# CON_SODIMM_200PIN_MO-224.net
KiCad netlist of a schematic drawn in Altium Designer
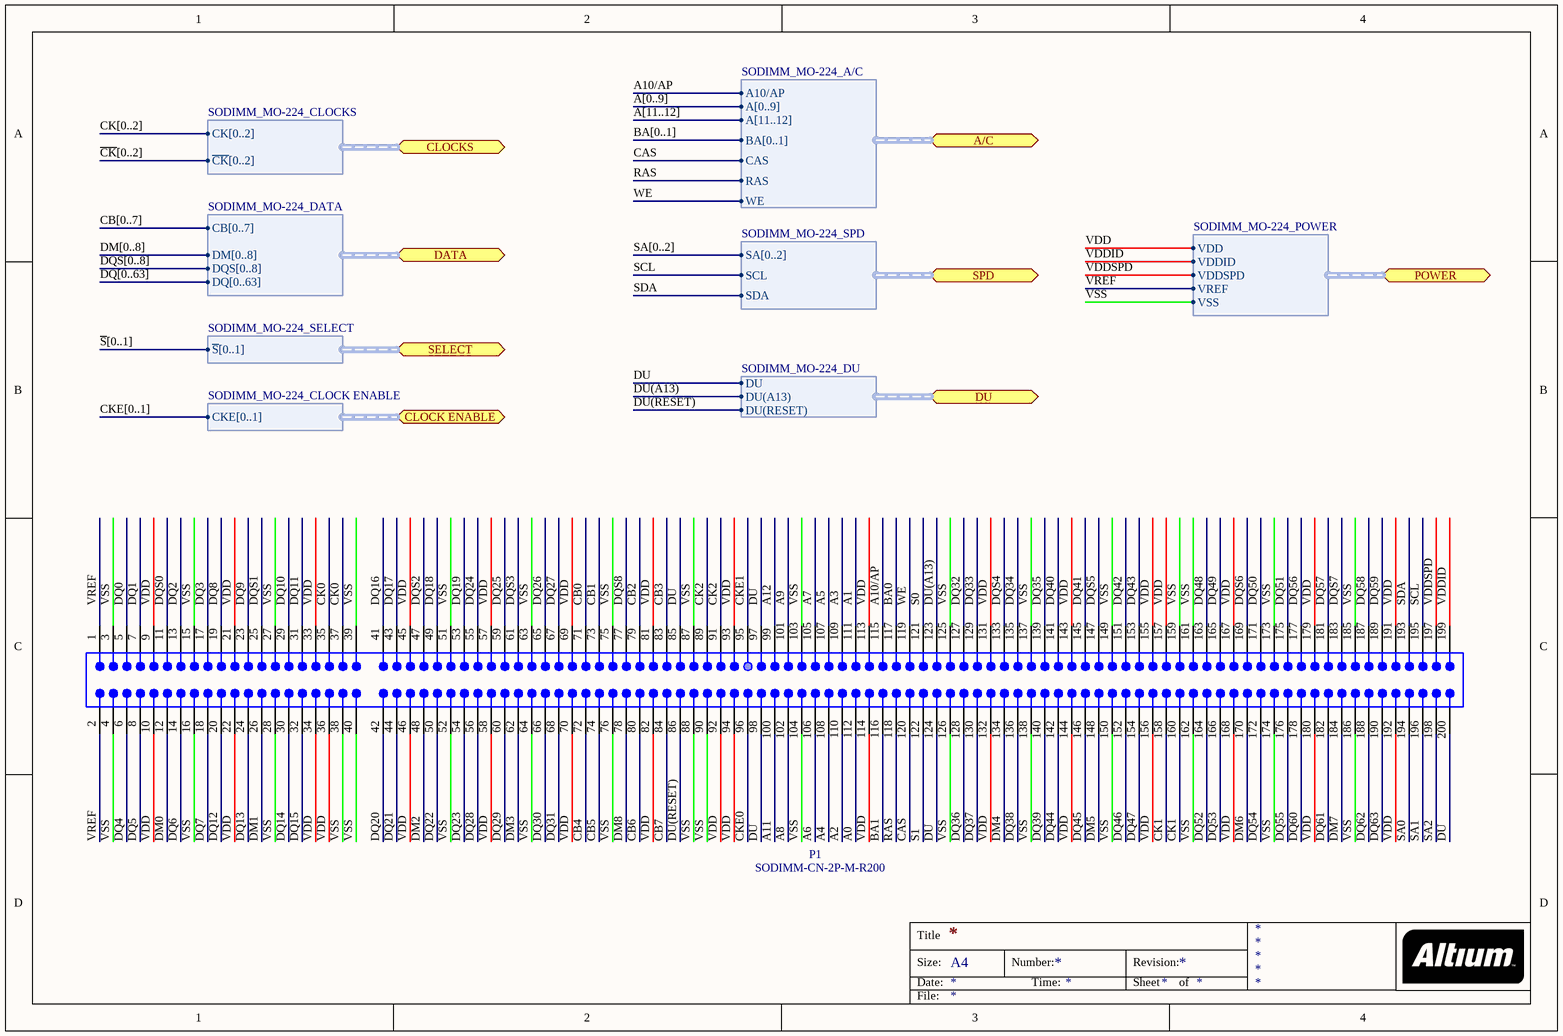
[diagram p0: CON_SODIMM_200PIN_MO-224.SchDoc]

(export (version "E")
  (design (tool "Eeschema 10.0.6"))
  (components
    (comp (ref "P1")
      (value "SODIMM-CN-2P-M-R200")
      (footprint "SODIMM-GF-2D-600-1K-S200")
      (description "Golden finger, SODIMM, Dual, Staggered, Pitch 0.6mm, 200-Position")
      (fields (field (name "PUBLISHER") "Altium"))
      (libsource (lib "Altium Shanghai") (part "SODIMM-CN-2S-M-R200"))
    )
  )
  (nets
    (net (code "10") (name "/A0") (class "Default")
      (node (ref "P1") (pin "112") (pinfunction "112_112") (pintype "passive"))
    )
    (net (code "11") (name "/A1") (class "Default")
      (node (ref "P1") (pin "111") (pinfunction "111_111") (pintype "passive"))
    )
    (net (code "12") (name "/A2") (class "Default")
      (node (ref "P1") (pin "110") (pinfunction "110_110") (pintype "passive"))
    )
    (net (code "13") (name "/A3") (class "Default")
      (node (ref "P1") (pin "109") (pinfunction "109_109") (pintype "passive"))
    )
    (net (code "14") (name "/A4") (class "Default")
      (node (ref "P1") (pin "108") (pinfunction "108_108") (pintype "passive"))
    )
    (net (code "15") (name "/A5") (class "Default")
      (node (ref "P1") (pin "107") (pinfunction "107_107") (pintype "passive"))
    )
    (net (code "16") (name "/A6") (class "Default")
      (node (ref "P1") (pin "106") (pinfunction "106_106") (pintype "passive"))
    )
    (net (code "17") (name "/A7") (class "Default")
      (node (ref "P1") (pin "105") (pinfunction "105_105") (pintype "passive"))
    )
    (net (code "18") (name "/A8") (class "Default")
      (node (ref "P1") (pin "102") (pinfunction "102_102") (pintype "passive"))
    )
    (net (code "19") (name "/A9") (class "Default")
      (node (ref "P1") (pin "101") (pinfunction "101_101") (pintype "passive"))
    )
    (net (code "20") (name "/A10{slash}AP") (class "Default")
      (node (ref "P1") (pin "115") (pinfunction "115_115") (pintype "passive"))
    )
    (net (code "21") (name "/A11") (class "Default")
      (node (ref "P1") (pin "100") (pinfunction "100_100") (pintype "passive"))
    )
    (net (code "22") (name "/A12") (class "Default")
      (node (ref "P1") (pin "99") (pinfunction "99_99") (pintype "passive"))
    )
    (net (code "25") (name "/BA0") (class "Default")
      (node (ref "P1") (pin "117") (pinfunction "117_117") (pintype "passive"))
    )
    (net (code "26") (name "/BA1") (class "Default")
      (node (ref "P1") (pin "116") (pinfunction "116_116") (pintype "passive"))
    )
    (net (code "28") (name "/CAS") (class "Default")
      (node (ref "P1") (pin "120") (pinfunction "120_120") (pintype "passive"))
    )
    (net (code "29") (name "/CB0") (class "Default")
      (node (ref "P1") (pin "71") (pinfunction "71_71") (pintype "passive"))
    )
    (net (code "30") (name "/CB1") (class "Default")
      (node (ref "P1") (pin "73") (pinfunction "73_73") (pintype "passive"))
    )
    (net (code "31") (name "/CB2") (class "Default")
      (node (ref "P1") (pin "79") (pinfunction "79_79") (pintype "passive"))
    )
    (net (code "32") (name "/CB3") (class "Default")
      (node (ref "P1") (pin "83") (pinfunction "83_83") (pintype "passive"))
    )
    (net (code "33") (name "/CB4") (class "Default")
      (node (ref "P1") (pin "72") (pinfunction "72_72") (pintype "passive"))
    )
    (net (code "34") (name "/CB5") (class "Default")
      (node (ref "P1") (pin "74") (pinfunction "74_74") (pintype "passive"))
    )
    (net (code "35") (name "/CB6") (class "Default")
      (node (ref "P1") (pin "80") (pinfunction "80_80") (pintype "passive"))
    )
    (net (code "36") (name "/CB7") (class "Default")
      (node (ref "P1") (pin "84") (pinfunction "84_84") (pintype "passive"))
    )
    (net (code "38") (name "/CK0") (class "Default")
      (node (ref "P1") (pin "35") (pinfunction "35_35") (pintype "passive"))
    )
    (net (code "39") (name "/CK1") (class "Default")
      (node (ref "P1") (pin "160") (pinfunction "160_160") (pintype "passive"))
    )
    (net (code "40") (name "/CK2") (class "Default")
      (node (ref "P1") (pin "89") (pinfunction "89_89") (pintype "passive"))
    )
    (net (code "41") (name "/CKE0") (class "Default")
      (node (ref "P1") (pin "96") (pinfunction "96_96") (pintype "passive"))
    )
    (net (code "42") (name "/CKE1") (class "Default")
      (node (ref "P1") (pin "95") (pinfunction "95_95") (pintype "passive"))
    )
    (net (code "45") (name "/DM0") (class "Default")
      (node (ref "P1") (pin "12") (pinfunction "12_12") (pintype "passive"))
    )
    (net (code "46") (name "/DM1") (class "Default")
      (node (ref "P1") (pin "26") (pinfunction "26_26") (pintype "passive"))
    )
    (net (code "47") (name "/DM2") (class "Default")
      (node (ref "P1") (pin "48") (pinfunction "48_48") (pintype "passive"))
    )
    (net (code "48") (name "/DM3") (class "Default")
      (node (ref "P1") (pin "62") (pinfunction "62_62") (pintype "passive"))
    )
    (net (code "49") (name "/DM4") (class "Default")
      (node (ref "P1") (pin "134") (pinfunction "134_134") (pintype "passive"))
    )
    (net (code "50") (name "/DM5") (class "Default")
      (node (ref "P1") (pin "148") (pinfunction "148_148") (pintype "passive"))
    )
    (net (code "51") (name "/DM6") (class "Default")
      (node (ref "P1") (pin "170") (pinfunction "170_170") (pintype "passive"))
    )
    (net (code "52") (name "/DM7") (class "Default")
      (node (ref "P1") (pin "184") (pinfunction "184_184") (pintype "passive"))
    )
    (net (code "53") (name "/DM8") (class "Default")
      (node (ref "P1") (pin "78") (pinfunction "78_78") (pintype "passive"))
    )
    (net (code "55") (name "/DQ0") (class "Default")
      (node (ref "P1") (pin "5") (pinfunction "5_5") (pintype "passive"))
    )
    (net (code "56") (name "/DQ1") (class "Default")
      (node (ref "P1") (pin "7") (pinfunction "7_7") (pintype "passive"))
    )
    (net (code "57") (name "/DQ2") (class "Default")
      (node (ref "P1") (pin "13") (pinfunction "13_13") (pintype "passive"))
    )
    (net (code "58") (name "/DQ3") (class "Default")
      (node (ref "P1") (pin "17") (pinfunction "17_17") (pintype "passive"))
    )
    (net (code "59") (name "/DQ4") (class "Default")
      (node (ref "P1") (pin "6") (pinfunction "6_6") (pintype "passive"))
    )
    (net (code "60") (name "/DQ5") (class "Default")
      (node (ref "P1") (pin "8") (pinfunction "8_8") (pintype "passive"))
    )
    (net (code "61") (name "/DQ6") (class "Default")
      (node (ref "P1") (pin "14") (pinfunction "14_14") (pintype "passive"))
    )
    (net (code "62") (name "/DQ7") (class "Default")
      (node (ref "P1") (pin "18") (pinfunction "18_18") (pintype "passive"))
    )
    (net (code "63") (name "/DQ8") (class "Default")
      (node (ref "P1") (pin "19") (pinfunction "19_19") (pintype "passive"))
    )
    (net (code "64") (name "/DQ9") (class "Default")
      (node (ref "P1") (pin "23") (pinfunction "23_23") (pintype "passive"))
    )
    (net (code "65") (name "/DQ10") (class "Default")
      (node (ref "P1") (pin "29") (pinfunction "29_29") (pintype "passive"))
    )
    (net (code "66") (name "/DQ11") (class "Default")
      (node (ref "P1") (pin "31") (pinfunction "31_31") (pintype "passive"))
    )
    (net (code "67") (name "/DQ12") (class "Default")
      (node (ref "P1") (pin "20") (pinfunction "20_20") (pintype "passive"))
    )
    (net (code "68") (name "/DQ13") (class "Default")
      (node (ref "P1") (pin "24") (pinfunction "24_24") (pintype "passive"))
    )
    (net (code "69") (name "/DQ14") (class "Default")
      (node (ref "P1") (pin "30") (pinfunction "30_30") (pintype "passive"))
    )
    (net (code "70") (name "/DQ15") (class "Default")
      (node (ref "P1") (pin "32") (pinfunction "32_32") (pintype "passive"))
    )
    (net (code "71") (name "/DQ16") (class "Default")
      (node (ref "P1") (pin "41") (pinfunction "41_41") (pintype "passive"))
    )
    (net (code "72") (name "/DQ17") (class "Default")
      (node (ref "P1") (pin "43") (pinfunction "43_43") (pintype "passive"))
    )
    (net (code "73") (name "/DQ18") (class "Default")
      (node (ref "P1") (pin "49") (pinfunction "49_49") (pintype "passive"))
    )
    (net (code "74") (name "/DQ19") (class "Default")
      (node (ref "P1") (pin "53") (pinfunction "53_53") (pintype "passive"))
    )
    (net (code "75") (name "/DQ20") (class "Default")
      (node (ref "P1") (pin "42") (pinfunction "42_42") (pintype "passive"))
    )
    (net (code "76") (name "/DQ21") (class "Default")
      (node (ref "P1") (pin "44") (pinfunction "44_44") (pintype "passive"))
    )
    (net (code "77") (name "/DQ22") (class "Default")
      (node (ref "P1") (pin "50") (pinfunction "50_50") (pintype "passive"))
    )
    (net (code "78") (name "/DQ23") (class "Default")
      (node (ref "P1") (pin "54") (pinfunction "54_54") (pintype "passive"))
    )
    (net (code "79") (name "/DQ24") (class "Default")
      (node (ref "P1") (pin "55") (pinfunction "55_55") (pintype "passive"))
    )
    (net (code "80") (name "/DQ25") (class "Default")
      (node (ref "P1") (pin "59") (pinfunction "59_59") (pintype "passive"))
    )
    (net (code "81") (name "/DQ26") (class "Default")
      (node (ref "P1") (pin "65") (pinfunction "65_65") (pintype "passive"))
    )
    (net (code "82") (name "/DQ27") (class "Default")
      (node (ref "P1") (pin "67") (pinfunction "67_67") (pintype "passive"))
    )
    (net (code "83") (name "/DQ28") (class "Default")
      (node (ref "P1") (pin "56") (pinfunction "56_56") (pintype "passive"))
    )
    (net (code "84") (name "/DQ29") (class "Default")
      (node (ref "P1") (pin "60") (pinfunction "60_60") (pintype "passive"))
    )
    (net (code "85") (name "/DQ30") (class "Default")
      (node (ref "P1") (pin "66") (pinfunction "66_66") (pintype "passive"))
    )
    (net (code "86") (name "/DQ31") (class "Default")
      (node (ref "P1") (pin "68") (pinfunction "68_68") (pintype "passive"))
    )
    (net (code "87") (name "/DQ32") (class "Default")
      (node (ref "P1") (pin "127") (pinfunction "127_127") (pintype "passive"))
    )
    (net (code "88") (name "/DQ33") (class "Default")
      (node (ref "P1") (pin "129") (pinfunction "129_129") (pintype "passive"))
    )
    (net (code "89") (name "/DQ34") (class "Default")
      (node (ref "P1") (pin "135") (pinfunction "135_135") (pintype "passive"))
    )
    (net (code "90") (name "/DQ35") (class "Default")
      (node (ref "P1") (pin "139") (pinfunction "139_139") (pintype "passive"))
    )
    (net (code "91") (name "/DQ36") (class "Default")
      (node (ref "P1") (pin "128") (pinfunction "128_128") (pintype "passive"))
    )
    (net (code "92") (name "/DQ37") (class "Default")
      (node (ref "P1") (pin "130") (pinfunction "130_130") (pintype "passive"))
    )
    (net (code "93") (name "/DQ38") (class "Default")
      (node (ref "P1") (pin "136") (pinfunction "136_136") (pintype "passive"))
    )
    (net (code "94") (name "/DQ39") (class "Default")
      (node (ref "P1") (pin "140") (pinfunction "140_140") (pintype "passive"))
    )
    (net (code "95") (name "/DQ40") (class "Default")
      (node (ref "P1") (pin "141") (pinfunction "141_141") (pintype "passive"))
    )
    (net (code "96") (name "/DQ41") (class "Default")
      (node (ref "P1") (pin "145") (pinfunction "145_145") (pintype "passive"))
    )
    (net (code "97") (name "/DQ42") (class "Default")
      (node (ref "P1") (pin "151") (pinfunction "151_151") (pintype "passive"))
    )
    (net (code "98") (name "/DQ43") (class "Default")
      (node (ref "P1") (pin "153") (pinfunction "153_153") (pintype "passive"))
    )
    (net (code "99") (name "/DQ44") (class "Default")
      (node (ref "P1") (pin "142") (pinfunction "142_142") (pintype "passive"))
    )
    (net (code "100") (name "/DQ45") (class "Default")
      (node (ref "P1") (pin "146") (pinfunction "146_146") (pintype "passive"))
    )
    (net (code "101") (name "/DQ46") (class "Default")
      (node (ref "P1") (pin "152") (pinfunction "152_152") (pintype "passive"))
    )
    (net (code "102") (name "/DQ47") (class "Default")
      (node (ref "P1") (pin "154") (pinfunction "154_154") (pintype "passive"))
    )
    (net (code "103") (name "/DQ48") (class "Default")
      (node (ref "P1") (pin "163") (pinfunction "163_163") (pintype "passive"))
    )
    (net (code "104") (name "/DQ49") (class "Default")
      (node (ref "P1") (pin "165") (pinfunction "165_165") (pintype "passive"))
    )
    (net (code "105") (name "/DQ50") (class "Default")
      (node (ref "P1") (pin "171") (pinfunction "171_171") (pintype "passive"))
    )
    (net (code "106") (name "/DQ51") (class "Default")
      (node (ref "P1") (pin "175") (pinfunction "175_175") (pintype "passive"))
    )
    (net (code "107") (name "/DQ52") (class "Default")
      (node (ref "P1") (pin "164") (pinfunction "164_164") (pintype "passive"))
    )
    (net (code "108") (name "/DQ53") (class "Default")
      (node (ref "P1") (pin "166") (pinfunction "166_166") (pintype "passive"))
    )
    (net (code "109") (name "/DQ54") (class "Default")
      (node (ref "P1") (pin "172") (pinfunction "172_172") (pintype "passive"))
    )
    (net (code "110") (name "/DQ55") (class "Default")
      (node (ref "P1") (pin "176") (pinfunction "176_176") (pintype "passive"))
    )
    (net (code "111") (name "/DQ56") (class "Default")
      (node (ref "P1") (pin "177") (pinfunction "177_177") (pintype "passive"))
    )
    (net (code "112") (name "/DQ57") (class "Default")
      (node (ref "P1") (pin "181") (pinfunction "181_181") (pintype "passive"))
    )
    (net (code "113") (name "/DQ58") (class "Default")
      (node (ref "P1") (pin "187") (pinfunction "187_187") (pintype "passive"))
    )
    (net (code "114") (name "/DQ59") (class "Default")
      (node (ref "P1") (pin "189") (pinfunction "189_189") (pintype "passive"))
    )
    (net (code "115") (name "/DQ60") (class "Default")
      (node (ref "P1") (pin "178") (pinfunction "178_178") (pintype "passive"))
    )
    (net (code "116") (name "/DQ61") (class "Default")
      (node (ref "P1") (pin "182") (pinfunction "182_182") (pintype "passive"))
    )
    (net (code "117") (name "/DQ62") (class "Default")
      (node (ref "P1") (pin "188") (pinfunction "188_188") (pintype "passive"))
    )
    (net (code "118") (name "/DQ63") (class "Default")
      (node (ref "P1") (pin "190") (pinfunction "190_190") (pintype "passive"))
    )
    (net (code "119") (name "/DQS0") (class "Default")
      (node (ref "P1") (pin "11") (pinfunction "11_11") (pintype "passive"))
    )
    (net (code "120") (name "/DQS1") (class "Default")
      (node (ref "P1") (pin "25") (pinfunction "25_25") (pintype "passive"))
    )
    (net (code "121") (name "/DQS2") (class "Default")
      (node (ref "P1") (pin "47") (pinfunction "47_47") (pintype "passive"))
    )
    (net (code "122") (name "/DQS3") (class "Default")
      (node (ref "P1") (pin "61") (pinfunction "61_61") (pintype "passive"))
    )
    (net (code "123") (name "/DQS4") (class "Default")
      (node (ref "P1") (pin "133") (pinfunction "133_133") (pintype "passive"))
    )
    (net (code "124") (name "/DQS5") (class "Default")
      (node (ref "P1") (pin "147") (pinfunction "147_147") (pintype "passive"))
    )
    (net (code "125") (name "/DQS6") (class "Default")
      (node (ref "P1") (pin "169") (pinfunction "169_169") (pintype "passive"))
    )
    (net (code "126") (name "/DQS7") (class "Default")
      (node (ref "P1") (pin "183") (pinfunction "183_183") (pintype "passive"))
    )
    (net (code "127") (name "/DQS8") (class "Default")
      (node (ref "P1") (pin "77") (pinfunction "77_77") (pintype "passive"))
    )
    (net (code "130") (name "/DU") (class "Default")
      (node (ref "P1") (pin "124") (pinfunction "124_124") (pintype "passive"))
      (node (ref "P1") (pin "200") (pinfunction "200_200") (pintype "passive"))
      (node (ref "P1") (pin "85") (pinfunction "85_85") (pintype "passive"))
      (node (ref "P1") (pin "97") (pinfunction "97_97") (pintype "passive"))
      (node (ref "P1") (pin "98") (pinfunction "98_98") (pintype "passive"))
    )
    (net (code "131") (name "/DU(A13)") (class "Default")
      (node (ref "P1") (pin "123") (pinfunction "123_123") (pintype "passive"))
    )
    (net (code "132") (name "/DU(RESET)") (class "Default")
      (node (ref "P1") (pin "86") (pinfunction "86_86") (pintype "passive"))
    )
    (net (code "133") (name "/RAS") (class "Default")
      (node (ref "P1") (pin "118") (pinfunction "118_118") (pintype "passive"))
    )
    (net (code "134") (name "/SA0") (class "Default")
      (node (ref "P1") (pin "194") (pinfunction "194_194") (pintype "passive"))
    )
    (net (code "135") (name "/SA1") (class "Default")
      (node (ref "P1") (pin "196") (pinfunction "196_196") (pintype "passive"))
    )
    (net (code "136") (name "/SA2") (class "Default")
      (node (ref "P1") (pin "198") (pinfunction "198_198") (pintype "passive"))
    )
    (net (code "138") (name "/SCL") (class "Default")
      (node (ref "P1") (pin "195") (pinfunction "195_195") (pintype "passive"))
    )
    (net (code "139") (name "/SDA") (class "Default")
      (node (ref "P1") (pin "193") (pinfunction "193_193") (pintype "passive"))
    )
    (net (code "140") (name "/VDD") (class "Default")
      (node (ref "P1") (pin "10") (pinfunction "10_10") (pintype "passive"))
      (node (ref "P1") (pin "113") (pinfunction "113_113") (pintype "passive"))
      (node (ref "P1") (pin "114") (pinfunction "114_114") (pintype "passive"))
      (node (ref "P1") (pin "131") (pinfunction "131_131") (pintype "passive"))
      (node (ref "P1") (pin "132") (pinfunction "132_132") (pintype "passive"))
      (node (ref "P1") (pin "143") (pinfunction "143_143") (pintype "passive"))
      (node (ref "P1") (pin "144") (pinfunction "144_144") (pintype "passive"))
      (node (ref "P1") (pin "155") (pinfunction "155_155") (pintype "passive"))
      (node (ref "P1") (pin "156") (pinfunction "156_156") (pintype "passive"))
      (node (ref "P1") (pin "157") (pinfunction "157_157") (pintype "passive"))
      (node (ref "P1") (pin "167") (pinfunction "167_167") (pintype "passive"))
      (node (ref "P1") (pin "168") (pinfunction "168_168") (pintype "passive"))
      (node (ref "P1") (pin "179") (pinfunction "179_179") (pintype "passive"))
      (node (ref "P1") (pin "180") (pinfunction "180_180") (pintype "passive"))
      (node (ref "P1") (pin "191") (pinfunction "191_191") (pintype "passive"))
      (node (ref "P1") (pin "192") (pinfunction "192_192") (pintype "passive"))
      (node (ref "P1") (pin "21") (pinfunction "21_21") (pintype "passive"))
      (node (ref "P1") (pin "22") (pinfunction "22_22") (pintype "passive"))
      (node (ref "P1") (pin "33") (pinfunction "33_33") (pintype "passive"))
      (node (ref "P1") (pin "34") (pinfunction "34_34") (pintype "passive"))
      (node (ref "P1") (pin "36") (pinfunction "36_36") (pintype "passive"))
      (node (ref "P1") (pin "45") (pinfunction "45_45") (pintype "passive"))
      (node (ref "P1") (pin "46") (pinfunction "46_46") (pintype "passive"))
      (node (ref "P1") (pin "57") (pinfunction "57_57") (pintype "passive"))
      (node (ref "P1") (pin "58") (pinfunction "58_58") (pintype "passive"))
      (node (ref "P1") (pin "69") (pinfunction "69_69") (pintype "passive"))
      (node (ref "P1") (pin "70") (pinfunction "70_70") (pintype "passive"))
      (node (ref "P1") (pin "81") (pinfunction "81_81") (pintype "passive"))
      (node (ref "P1") (pin "82") (pinfunction "82_82") (pintype "passive"))
      (node (ref "P1") (pin "9") (pinfunction "9_9") (pintype "passive"))
      (node (ref "P1") (pin "92") (pinfunction "92_92") (pintype "passive"))
      (node (ref "P1") (pin "93") (pinfunction "93_93") (pintype "passive"))
      (node (ref "P1") (pin "94") (pinfunction "94_94") (pintype "passive"))
    )
    (net (code "141") (name "/VDDID") (class "Default")
      (node (ref "P1") (pin "199") (pinfunction "199_199") (pintype "passive"))
    )
    (net (code "142") (name "/VDDSPD") (class "Default")
      (node (ref "P1") (pin "197") (pinfunction "197_197") (pintype "passive"))
    )
    (net (code "143") (name "/VREF") (class "Default")
      (node (ref "P1") (pin "1") (pinfunction "1_1") (pintype "passive"))
      (node (ref "P1") (pin "2") (pinfunction "2_2") (pintype "passive"))
    )
    (net (code "144") (name "/VSS") (class "Default")
      (node (ref "P1") (pin "103") (pinfunction "103_103") (pintype "passive"))
      (node (ref "P1") (pin "104") (pinfunction "104_104") (pintype "passive"))
      (node (ref "P1") (pin "125") (pinfunction "125_125") (pintype "passive"))
      (node (ref "P1") (pin "126") (pinfunction "126_126") (pintype "passive"))
      (node (ref "P1") (pin "137") (pinfunction "137_137") (pintype "passive"))
      (node (ref "P1") (pin "138") (pinfunction "138_138") (pintype "passive"))
      (node (ref "P1") (pin "149") (pinfunction "149_149") (pintype "passive"))
      (node (ref "P1") (pin "15") (pinfunction "15_15") (pintype "passive"))
      (node (ref "P1") (pin "150") (pinfunction "150_150") (pintype "passive"))
      (node (ref "P1") (pin "159") (pinfunction "159_159") (pintype "passive"))
      (node (ref "P1") (pin "16") (pinfunction "16_16") (pintype "passive"))
      (node (ref "P1") (pin "161") (pinfunction "161_161") (pintype "passive"))
      (node (ref "P1") (pin "162") (pinfunction "162_162") (pintype "passive"))
      (node (ref "P1") (pin "173") (pinfunction "173_173") (pintype "passive"))
      (node (ref "P1") (pin "174") (pinfunction "174_174") (pintype "passive"))
      (node (ref "P1") (pin "185") (pinfunction "185_185") (pintype "passive"))
      (node (ref "P1") (pin "186") (pinfunction "186_186") (pintype "passive"))
      (node (ref "P1") (pin "27") (pinfunction "27_27") (pintype "passive"))
      (node (ref "P1") (pin "28") (pinfunction "28_28") (pintype "passive"))
      (node (ref "P1") (pin "3") (pinfunction "3_3") (pintype "passive"))
      (node (ref "P1") (pin "38") (pinfunction "38_38") (pintype "passive"))
      (node (ref "P1") (pin "39") (pinfunction "39_39") (pintype "passive"))
      (node (ref "P1") (pin "4") (pinfunction "4_4") (pintype "passive"))
      (node (ref "P1") (pin "40") (pinfunction "40_40") (pintype "passive"))
      (node (ref "P1") (pin "51") (pinfunction "51_51") (pintype "passive"))
      (node (ref "P1") (pin "52") (pinfunction "52_52") (pintype "passive"))
      (node (ref "P1") (pin "63") (pinfunction "63_63") (pintype "passive"))
      (node (ref "P1") (pin "64") (pinfunction "64_64") (pintype "passive"))
      (node (ref "P1") (pin "75") (pinfunction "75_75") (pintype "passive"))
      (node (ref "P1") (pin "76") (pinfunction "76_76") (pintype "passive"))
      (node (ref "P1") (pin "87") (pinfunction "87_87") (pintype "passive"))
      (node (ref "P1") (pin "88") (pinfunction "88_88") (pintype "passive"))
      (node (ref "P1") (pin "90") (pinfunction "90_90") (pintype "passive"))
    )
    (net (code "145") (name "/WE") (class "Default")
      (node (ref "P1") (pin "119") (pinfunction "119_119") (pintype "passive"))
    )
    (net (code "154") (name "/~{CK}0") (class "Default")
      (node (ref "P1") (pin "37") (pinfunction "37_37") (pintype "passive"))
    )
    (net (code "155") (name "/~{CK}1") (class "Default")
      (node (ref "P1") (pin "158") (pinfunction "158_158") (pintype "passive"))
    )
    (net (code "156") (name "/~{CK}2") (class "Default")
      (node (ref "P1") (pin "91") (pinfunction "91_91") (pintype "passive"))
    )
    (net (code "158") (name "/~{S}0") (class "Default")
      (node (ref "P1") (pin "121") (pinfunction "121_121") (pintype "passive"))
    )
    (net (code "159") (name "/~{S}1") (class "Default")
      (node (ref "P1") (pin "122") (pinfunction "122_122") (pintype "passive"))
    )
  )
)
